# Synch_Demof.net
KiCad netlist of a schematic drawn in Altium Designer
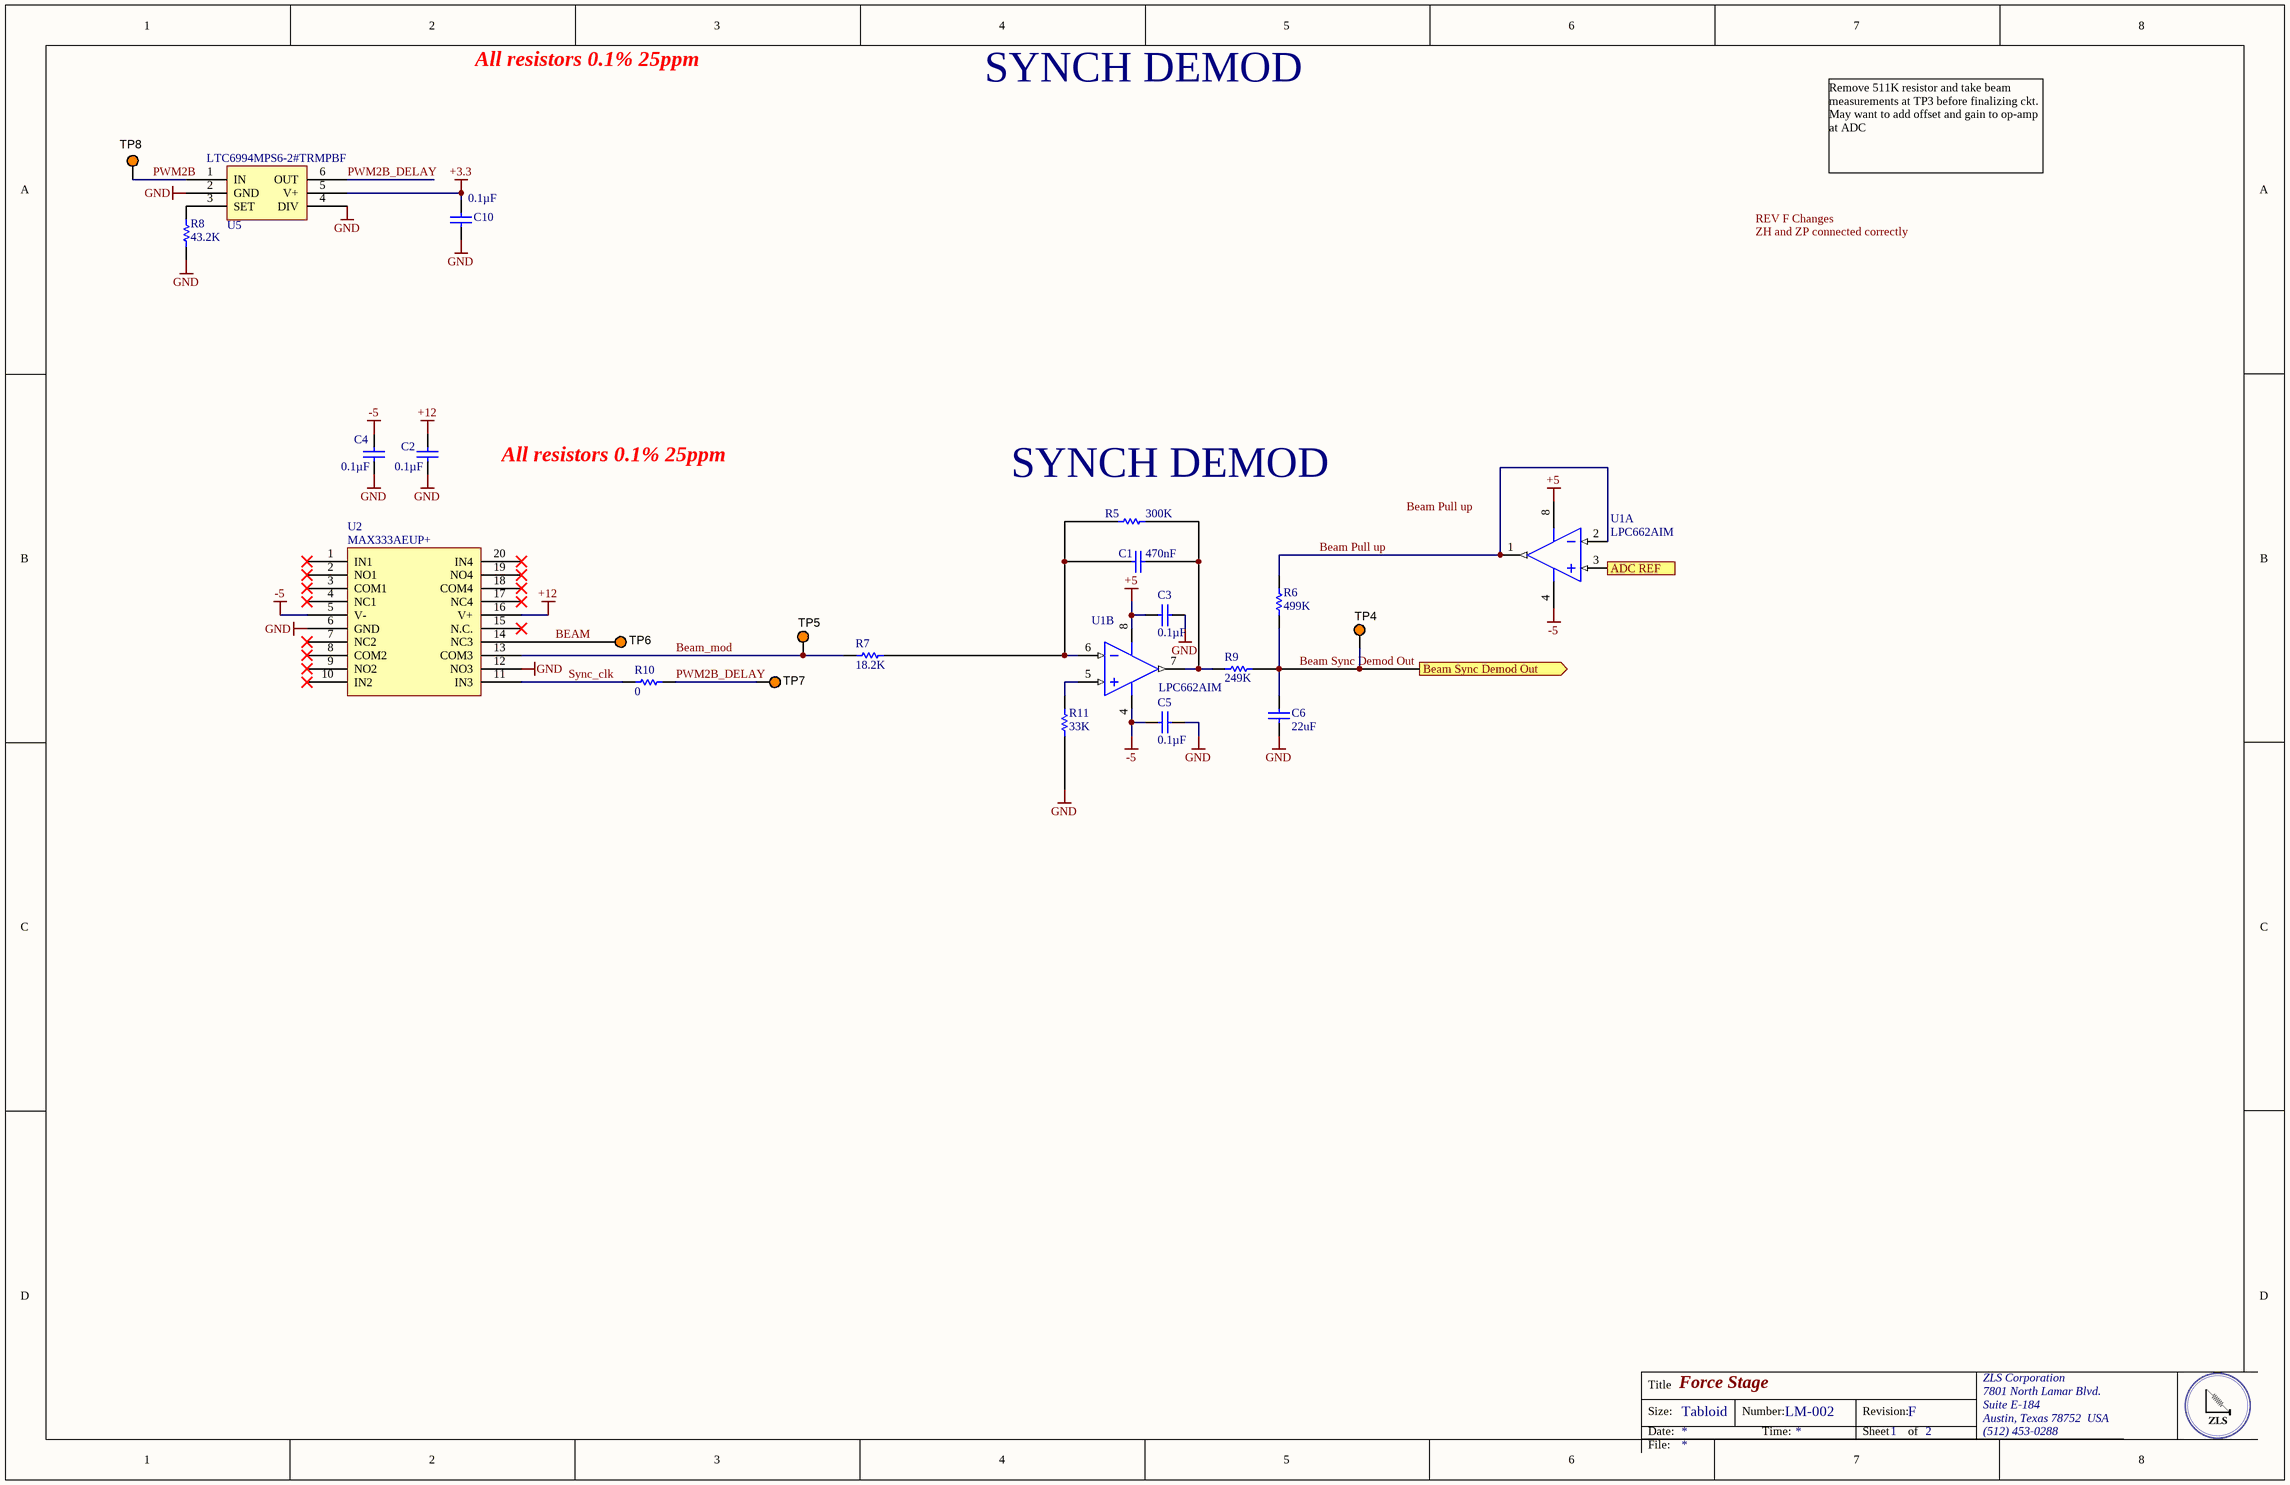
[diagram p0: Synch_Demof.SchDoc]

(export (version "E")
  (design (tool "Eeschema 10.0.6"))
  (components
    (comp (ref "C1")
      (value "470nF")
      (footprint "CAPC0805(2012)75_L")
      (description "CAP CER 0.47UF 25V X7R 0805")
      (fields
        (field (name "MANUFACTURER") "Murata Electronics North America")
        (field (name "MANUFACTURER PART NUMBER") "GRM219R71E474KA88D")
      )
      (libsource (lib "Altium Content Vault") (part "CMP-1036-02117-1"))
    )
    (comp (ref "C2")
      (value "CAP CER 0.1UF 25V X7R 0805")
      (footprint "CAPC0805(2012)145_N")
      (fields
        (field (name "MANUFACTURER") "Murata Electronics North America")
        (field (name "MANUFACTURER PART NUMBER") "GRM21BR71E104KA01L")
        (field (name "CAPACITANCE") "0.1µF")
        (field (name "TOLERANCE") "±10%")
      )
      (libsource (lib "Altium Content Vault") (part "CMP-1036-04795-1"))
    )
    (comp (ref "C3")
      (value "CAP CER 0.1UF 25V X7R 0805")
      (footprint "CAPC0805(2012)145_N")
      (fields
        (field (name "MANUFACTURER") "Murata Electronics North America")
        (field (name "MANUFACTURER PART NUMBER") "GRM21BR71E104KA01L")
        (field (name "CAPACITANCE") "0.1µF")
        (field (name "TOLERANCE") "±10%")
      )
      (libsource (lib "Altium Content Vault") (part "CMP-1036-04795-1"))
    )
    (comp (ref "C4")
      (value "CAP CER 0.1UF 25V X7R 0805")
      (footprint "CAPC0805(2012)145_N")
      (fields
        (field (name "MANUFACTURER") "Murata Electronics North America")
        (field (name "MANUFACTURER PART NUMBER") "GRM21BR71E104KA01L")
        (field (name "CAPACITANCE") "0.1µF")
        (field (name "TOLERANCE") "±10%")
      )
      (libsource (lib "Altium Content Vault") (part "CMP-1036-04795-1"))
    )
    (comp (ref "C5")
      (value "CAP CER 0.1UF 25V X7R 0805")
      (footprint "CAPC0805(2012)145_N")
      (fields
        (field (name "MANUFACTURER") "Murata Electronics North America")
        (field (name "MANUFACTURER PART NUMBER") "GRM21BR71E104KA01L")
        (field (name "CAPACITANCE") "0.1µF")
        (field (name "TOLERANCE") "±10%")
      )
      (libsource (lib "Altium Content Vault") (part "CMP-1036-04795-1"))
    )
    (comp (ref "C6")
      (value "22uF")
      (footprint "CAPC0805(2012)75_L")
      (description "CAP CER 22UF 25V X5R 0805")
      (fields
        (field (name "MANUFACTURER") "Murata Electronics North America")
        (field (name "MANUFACTURER PART NUMBER") "GRM21BR61E226ME44L")
      )
      (libsource (lib "Altium Content Vault") (part "CMP-1036-02117-1"))
    )
    (comp (ref "C10")
      (value "CAP CER 0.1UF 25V X7R 0805")
      (footprint "CAPC0805(2012)145_N")
      (fields
        (field (name "MANUFACTURER") "Murata Electronics North America")
        (field (name "MANUFACTURER PART NUMBER") "GRM21BR71E104KA01L")
        (field (name "CAPACITANCE") "0.1µF")
        (field (name "TOLERANCE") "±10%")
      )
      (libsource (lib "Altium Content Vault") (part "CMP-1036-04795-1"))
    )
    (comp (ref "R5")
      (value "300K")
      (footprint "RESC0805(2012)_L")
      (description "RES SMD 300K OHM 1% 1/8W 0805")
      (fields
        (field (name "MANUFACTURER") "Vishay Dale")
        (field (name "MANUFACTURER PART NUMBER") "CRCW0805300KFKEAHP")
      )
      (libsource (lib "Altium Content Vault") (part "CMP-1013-00215-1"))
    )
    (comp (ref "R6")
      (value "499K")
      (footprint "RESC0805(2012)_L")
      (description "RES SMD 499K OHM 0.1% 1/8W 0805")
      (fields
        (field (name "MANUFACTURER") "Panasonic Electronic Components")
        (field (name "MANUFACTURER PART NUMBER") "ERA-6AEB4993V")
      )
      (libsource (lib "Altium Content Vault") (part "CMP-1013-00215-1"))
    )
    (comp (ref "R7")
      (value "18.2K")
      (footprint "RESC0805(2012)_L")
      (description "RES SMD 18.2K OHM 1% 1/8W 0805")
      (fields
        (field (name "MANUFACTURER") "Panasonic Electronic Components")
        (field (name "MANUFACTURER PART NUMBER") "ERJ-6ENF1822V")
      )
      (libsource (lib "Altium Content Vault") (part "CMP-1013-00215-1"))
    )
    (comp (ref "R8")
      (value "43.2K")
      (footprint "RESC0805(2012)_L")
      (description "RES SMD 43.2K OHM 1% 1/8W 0805")
      (fields
        (field (name "MANUFACTURER") "Vishay Dale")
        (field (name "MANUFACTURER PART NUMBER") "CRCW080543K2FKEA")
      )
      (libsource (lib "Altium Content Vault") (part "CMP-1013-00215-1"))
    )
    (comp (ref "R9")
      (value "249K")
      (footprint "RESC0805(2012)_L")
      (description "RES SMD 249K OHM 0.1% 1/8W 0805")
      (fields
        (field (name "MANUFACTURER") "Panasonic Electronic Components")
        (field (name "MANUFACTURER PART NUMBER") "ERA-6AEB2493V")
      )
      (libsource (lib "Altium Content Vault") (part "CMP-1013-00215-1"))
    )
    (comp (ref "R10")
      (value "0")
      (footprint "RESC0805(2012)_L")
      (description "RES SMD 0 OHM JUMPER 1/8W 0805")
      (fields
        (field (name "MANUFACTURER") "Panasonic Electronic Components")
        (field (name "MANUFACTURER PART NUMBER") "ERJ-6GEY0R00V")
      )
      (libsource (lib "Altium Content Vault") (part "CMP-1013-00215-1"))
    )
    (comp (ref "R11")
      (value "33K")
      (footprint "RESC0805(2012)_L")
      (description "RES SMD 33K OHM 1% 1/2W 0805")
      (fields
        (field (name "MANUFACTURER") "Vishay Dale")
        (field (name "MANUFACTURER PART NUMBER") "CRCW080533K0FKEAHP")
      )
      (libsource (lib "Altium Content Vault") (part "CMP-1013-00215-1"))
    )
    (comp (ref "TP4")
      (value "5003")
      (footprint "KSTN-5003")
      (description "Test Point, Orange, 1-Pin THD, RoHS")
      (libsource (lib "Altium Content Vault") (part "CMP-1672-00009-1"))
    )
    (comp (ref "TP5")
      (value "5003")
      (footprint "KSTN-5003")
      (description "Test Point, Orange, 1-Pin THD, RoHS")
      (libsource (lib "Altium Content Vault") (part "CMP-1672-00009-1"))
    )
    (comp (ref "TP6")
      (value "5003")
      (footprint "KSTN-5003")
      (description "Test Point, Orange, 1-Pin THD, RoHS")
      (libsource (lib "Altium Content Vault") (part "CMP-1672-00009-1"))
    )
    (comp (ref "TP7")
      (value "5003")
      (footprint "KSTN-5003")
      (description "Test Point, Orange, 1-Pin THD, RoHS")
      (libsource (lib "Altium Content Vault") (part "CMP-1672-00009-1"))
    )
    (comp (ref "TP8")
      (value "5003")
      (footprint "KSTN-5003")
      (description "Test Point, Orange, 1-Pin THD, RoHS")
      (libsource (lib "Altium Content Vault") (part "CMP-1672-00009-1"))
    )
    (comp (ref "U1")
      (value "LPC662AIM")
      (footprint "D0008A_M")
      (description "Low Power CMOS Dual Operational Amplifier, 8-pin Narrow SOIC")
      (fields
        (field (name "MANUFACTURER") "Texas Instruments")
        (field (name "MANUFACTURER PART NUMBER") "LPC662AIM/NOPB")
      )
      (libsource (lib "Altium Content Vault") (part "CMP-0055-00867-3"))
    )
    (comp (ref "U2")
      (value "MAX333AEUP+")
      (footprint "TSOP65P640X90-20N")
      (description "IC SWITCH QUAD SPDT 20TSSOP")
      (fields (field (name "MANUFACTURER") "Maxim Integrated") (field (name "BASE PART NUMBER") "MAX333"))
      (libsource (lib "ZLS_Schematic_lib") (part "MAX333CWP+"))
    )
    (comp (ref "U5")
      (value "LTC6994MPS6-2#TRMPBF")
      (footprint "LTC6994MPS6-2#TRMPBF")
      (description "IC DELAY BLOCK 8TAP PROG TSOT23")
      (fields
        (field (name "MANUFACTURER") "Linear Technology/Analog Devices")
        (field (name "MANUFACTURER PART NUMBER") "LTC6994CS6-2#TRMPBF")
      )
      (libsource (lib "ZLS_Schematic_lib") (part "LTC6994MPS6-2#TRMPBF"))
    )
  )
  (nets
    (net (code "1") (name "+3.3") (class "Default")
      (node (ref "C10") (pin "1") (pinfunction "1_1") (pintype "passive"))
      (node (ref "U5") (pin "5") (pinfunction "V+_5") (pintype "passive"))
    )
    (net (code "2") (name "+5") (class "Default")
      (node (ref "C3") (pin "1") (pinfunction "1_1") (pintype "passive"))
      (node (ref "U1") (pin "8") (pinfunction "V+_8") (pintype "power_in"))
    )
    (net (code "3") (name "+12") (class "Default")
      (node (ref "C2") (pin "1") (pinfunction "1_1") (pintype "passive"))
      (node (ref "U2") (pin "16") (pinfunction "V+_16") (pintype "power_in"))
    )
    (net (code "4") (name "-5") (class "Default")
      (node (ref "C4") (pin "1") (pinfunction "1_1") (pintype "passive"))
      (node (ref "C5") (pin "1") (pinfunction "1_1") (pintype "passive"))
      (node (ref "U1") (pin "4") (pinfunction "V-_4") (pintype "power_in"))
      (node (ref "U2") (pin "5") (pinfunction "V-_5") (pintype "power_in"))
    )
    (net (code "5") (name "/ADC REF") (class "Default")
      (node (ref "U1") (pin "3") (pinfunction "INA+_3") (pintype "input"))
    )
    (net (code "6") (name "/BEAM") (class "Default")
      (node (ref "TP6") (pin "1") (pinfunction "1_1") (pintype "passive"))
      (node (ref "U2") (pin "14") (pinfunction "NC3_14") (pintype "passive"))
    )
    (net (code "7") (name "/Beam Pull up") (class "Default")
      (node (ref "R6") (pin "2") (pinfunction "2_2") (pintype "passive"))
      (node (ref "U1") (pin "1") (pinfunction "OUTA_1") (pintype "output"))
      (node (ref "U1") (pin "2") (pinfunction "INA-_2") (pintype "input"))
    )
    (net (code "8") (name "/Beam Sync Demod Out") (class "Default")
      (node (ref "C6") (pin "2") (pinfunction "2_2") (pintype "passive"))
      (node (ref "R6") (pin "1") (pinfunction "1_1") (pintype "passive"))
      (node (ref "R9") (pin "1") (pinfunction "1_1") (pintype "passive"))
      (node (ref "TP4") (pin "1") (pinfunction "1_1") (pintype "passive"))
    )
    (net (code "9") (name "/Beam_mod") (class "Default")
      (node (ref "R7") (pin "2") (pinfunction "2_2") (pintype "passive"))
      (node (ref "TP5") (pin "1") (pinfunction "1_1") (pintype "passive"))
      (node (ref "U2") (pin "13") (pinfunction "COM3_13") (pintype "passive"))
    )
    (net (code "10") (name "/PWM2B") (class "Default")
      (node (ref "TP8") (pin "1") (pinfunction "1_1") (pintype "passive"))
      (node (ref "U5") (pin "1") (pinfunction "IN_1") (pintype "passive"))
    )
    (net (code "11") (name "/PWM2B_DELAY") (class "Default")
      (node (ref "R10") (pin "1") (pinfunction "1_1") (pintype "passive"))
      (node (ref "TP7") (pin "1") (pinfunction "1_1") (pintype "passive"))
      (node (ref "U5") (pin "6") (pinfunction "OUT_6") (pintype "passive"))
    )
    (net (code "13") (name "/Sync_clk") (class "Default")
      (node (ref "R10") (pin "2") (pinfunction "2_2") (pintype "passive"))
      (node (ref "U2") (pin "11") (pinfunction "IN3_11") (pintype "passive"))
    )
    (net (code "15") (name "GND") (class "Default")
      (node (ref "C10") (pin "2") (pinfunction "2_2") (pintype "passive"))
      (node (ref "C2") (pin "2") (pinfunction "2_2") (pintype "passive"))
      (node (ref "C3") (pin "2") (pinfunction "2_2") (pintype "passive"))
      (node (ref "C4") (pin "2") (pinfunction "2_2") (pintype "passive"))
      (node (ref "C5") (pin "2") (pinfunction "2_2") (pintype "passive"))
      (node (ref "C6") (pin "1") (pinfunction "1_1") (pintype "passive"))
      (node (ref "R11") (pin "1") (pinfunction "1_1") (pintype "passive"))
      (node (ref "R8") (pin "2") (pinfunction "2_2") (pintype "passive"))
      (node (ref "U2") (pin "12") (pinfunction "NO3_12") (pintype "passive"))
      (node (ref "U2") (pin "6") (pinfunction "GND_6") (pintype "passive"))
      (node (ref "U5") (pin "2") (pinfunction "GND_2") (pintype "passive"))
      (node (ref "U5") (pin "4") (pinfunction "DIV_4") (pintype "passive"))
    )
    (net (code "16") (name "Net-(U1B-INB+)") (class "Default")
      (node (ref "R11") (pin "2") (pinfunction "2_2") (pintype "passive"))
      (node (ref "U1") (pin "5") (pinfunction "INB+_5") (pintype "input"))
    )
    (net (code "17") (name "Net-(U1B-INB-)") (class "Default")
      (node (ref "C1") (pin "1") (pinfunction "1_1") (pintype "passive"))
      (node (ref "R5") (pin "2") (pinfunction "2_2") (pintype "passive"))
      (node (ref "R7") (pin "1") (pinfunction "1_1") (pintype "passive"))
      (node (ref "U1") (pin "6") (pinfunction "INB-_6") (pintype "input"))
    )
    (net (code "18") (name "Net-(U1B-OUTB)") (class "Default")
      (node (ref "C1") (pin "2") (pinfunction "2_2") (pintype "passive"))
      (node (ref "R5") (pin "1") (pinfunction "1_1") (pintype "passive"))
      (node (ref "R9") (pin "2") (pinfunction "2_2") (pintype "passive"))
      (node (ref "U1") (pin "7") (pinfunction "OUTB_7") (pintype "output"))
    )
    (net (code "19") (name "Net-(U5-SET)") (class "Default")
      (node (ref "R8") (pin "1") (pinfunction "1_1") (pintype "passive"))
      (node (ref "U5") (pin "3") (pinfunction "SET_3") (pintype "passive"))
    )
    (net (code "20") (name "unconnected-(U2-COM1-Pad3)") (class "Default")
      (node (ref "U2") (pin "3") (pinfunction "COM1_3") (pintype "passive+no_connect"))
    )
    (net (code "21") (name "unconnected-(U2-COM2-Pad8)") (class "Default")
      (node (ref "U2") (pin "8") (pinfunction "COM2_8") (pintype "passive+no_connect"))
    )
    (net (code "22") (name "unconnected-(U2-COM4-Pad18)") (class "Default")
      (node (ref "U2") (pin "18") (pinfunction "COM4_18") (pintype "passive+no_connect"))
    )
    (net (code "23") (name "unconnected-(U2-IN1-Pad1)") (class "Default")
      (node (ref "U2") (pin "1") (pinfunction "IN1_1") (pintype "passive+no_connect"))
    )
    (net (code "24") (name "unconnected-(U2-IN2-Pad10)") (class "Default")
      (node (ref "U2") (pin "10") (pinfunction "IN2_10") (pintype "passive+no_connect"))
    )
    (net (code "25") (name "unconnected-(U2-IN4-Pad20)") (class "Default")
      (node (ref "U2") (pin "20") (pinfunction "IN4_20") (pintype "passive+no_connect"))
    )
    (net (code "26") (name "unconnected-(U2-N.C.-Pad15)") (class "Default")
      (node (ref "U2") (pin "15") (pinfunction "N.C._15") (pintype "passive+no_connect"))
    )
    (net (code "27") (name "unconnected-(U2-NC1-Pad4)") (class "Default")
      (node (ref "U2") (pin "4") (pinfunction "NC1_4") (pintype "passive+no_connect"))
    )
    (net (code "28") (name "unconnected-(U2-NC2-Pad7)") (class "Default")
      (node (ref "U2") (pin "7") (pinfunction "NC2_7") (pintype "passive+no_connect"))
    )
    (net (code "29") (name "unconnected-(U2-NC4-Pad17)") (class "Default")
      (node (ref "U2") (pin "17") (pinfunction "NC4_17") (pintype "passive+no_connect"))
    )
    (net (code "30") (name "unconnected-(U2-NO1-Pad2)") (class "Default")
      (node (ref "U2") (pin "2") (pinfunction "NO1_2") (pintype "passive+no_connect"))
    )
    (net (code "31") (name "unconnected-(U2-NO2-Pad9)") (class "Default")
      (node (ref "U2") (pin "9") (pinfunction "NO2_9") (pintype "passive+no_connect"))
    )
    (net (code "32") (name "unconnected-(U2-NO4-Pad19)") (class "Default")
      (node (ref "U2") (pin "19") (pinfunction "NO4_19") (pintype "passive+no_connect"))
    )
  )
)
